# kb2040.net
KiCad netlist of a schematic drawn in EAGLE
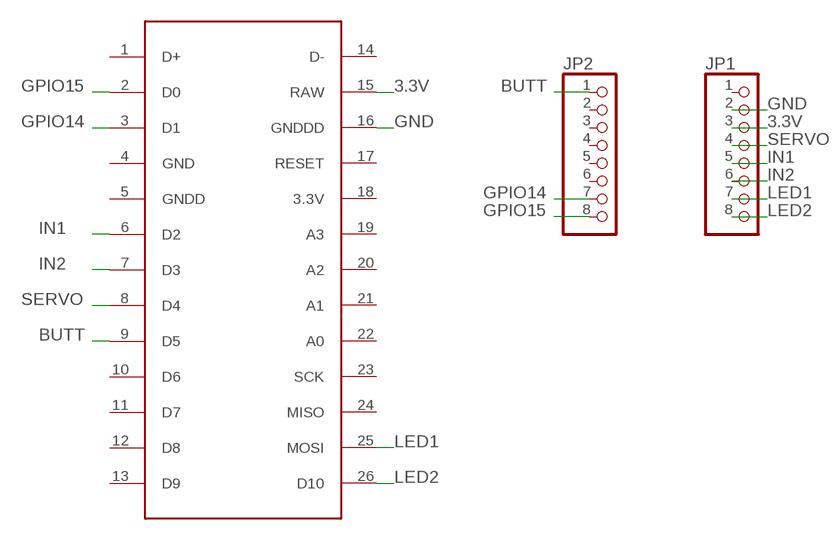
[diagram p0: schematic, sheet 1]

(export (version "E")
  (design (tool "Eeschema 10.0.6"))
  (components
    (comp (ref "JP1")
      (value "PINHD-1X8")
      (footprint "eagle-import:1X08")
      (libsource (lib "eagle-import") (part "PINHD-1X8"))
    )
    (comp (ref "JP2")
      (value "PINHD-1X8")
      (footprint "eagle-import:1X08")
      (libsource (lib "eagle-import") (part "PINHD-1X8"))
    )
    (comp (ref "U$1")
      (value "KB2040")
      (footprint "eagle-import:KB2040")
      (libsource (lib "eagle-import") (part "KB2040"))
    )
  )
  (nets
    (net (code "1") (name "/3.3V") (class "Default")
      (node (ref "JP1") (pin "3") (pinfunction "3_3") (pintype "passive"))
      (node (ref "U$1") (pin "15") (pinfunction "RAW_15") (pintype "bidirectional"))
    )
    (net (code "2") (name "/BUTT") (class "Default")
      (node (ref "JP2") (pin "1") (pinfunction "1_1") (pintype "passive"))
      (node (ref "U$1") (pin "9") (pinfunction "D5_9") (pintype "bidirectional"))
    )
    (net (code "3") (name "/GND") (class "Default")
      (node (ref "JP1") (pin "2") (pinfunction "2_2") (pintype "passive"))
      (node (ref "U$1") (pin "16") (pinfunction "GNDDD_16") (pintype "bidirectional"))
    )
    (net (code "4") (name "/GPIO14") (class "Default")
      (node (ref "JP2") (pin "7") (pinfunction "7_7") (pintype "passive"))
      (node (ref "U$1") (pin "3") (pinfunction "D1_3") (pintype "bidirectional"))
    )
    (net (code "5") (name "/GPIO15") (class "Default")
      (node (ref "JP2") (pin "8") (pinfunction "8_8") (pintype "passive"))
      (node (ref "U$1") (pin "2") (pinfunction "D0_2") (pintype "bidirectional"))
    )
    (net (code "6") (name "/IN1") (class "Default")
      (node (ref "JP1") (pin "5") (pinfunction "5_5") (pintype "passive"))
      (node (ref "U$1") (pin "6") (pinfunction "D2_6") (pintype "bidirectional"))
    )
    (net (code "7") (name "/IN2") (class "Default")
      (node (ref "JP1") (pin "6") (pinfunction "6_6") (pintype "passive"))
      (node (ref "U$1") (pin "7") (pinfunction "D3_7") (pintype "bidirectional"))
    )
    (net (code "8") (name "/LED1") (class "Default")
      (node (ref "JP1") (pin "7") (pinfunction "7_7") (pintype "passive"))
      (node (ref "U$1") (pin "25") (pinfunction "MOSI_25") (pintype "bidirectional"))
    )
    (net (code "9") (name "/LED2") (class "Default")
      (node (ref "JP1") (pin "8") (pinfunction "8_8") (pintype "passive"))
      (node (ref "U$1") (pin "26") (pinfunction "D10_26") (pintype "bidirectional"))
    )
    (net (code "10") (name "/SERVO") (class "Default")
      (node (ref "JP1") (pin "4") (pinfunction "4_4") (pintype "passive"))
      (node (ref "U$1") (pin "8") (pinfunction "D4_8") (pintype "bidirectional"))
    )
    (net (code "11") (name "unconnected-(JP1-Pad1)") (class "Default")
      (node (ref "JP1") (pin "1") (pinfunction "1_1") (pintype "passive"))
    )
    (net (code "12") (name "unconnected-(JP2-Pad2)") (class "Default")
      (node (ref "JP2") (pin "2") (pinfunction "2_2") (pintype "passive"))
    )
    (net (code "13") (name "unconnected-(JP2-Pad3)") (class "Default")
      (node (ref "JP2") (pin "3") (pinfunction "3_3") (pintype "passive"))
    )
    (net (code "14") (name "unconnected-(JP2-Pad4)") (class "Default")
      (node (ref "JP2") (pin "4") (pinfunction "4_4") (pintype "passive"))
    )
    (net (code "15") (name "unconnected-(JP2-Pad5)") (class "Default")
      (node (ref "JP2") (pin "5") (pinfunction "5_5") (pintype "passive"))
    )
    (net (code "16") (name "unconnected-(JP2-Pad6)") (class "Default")
      (node (ref "JP2") (pin "6") (pinfunction "6_6") (pintype "passive"))
    )
    (net (code "17") (name "unconnected-(U$1-3.3V-Pad18)") (class "Default")
      (node (ref "U$1") (pin "18") (pinfunction "3.3V_18") (pintype "bidirectional"))
    )
    (net (code "18") (name "unconnected-(U$1-A0-Pad22)") (class "Default")
      (node (ref "U$1") (pin "22") (pinfunction "A0_22") (pintype "bidirectional"))
    )
    (net (code "19") (name "unconnected-(U$1-A1-Pad21)") (class "Default")
      (node (ref "U$1") (pin "21") (pinfunction "A1_21") (pintype "bidirectional"))
    )
    (net (code "20") (name "unconnected-(U$1-A2-Pad20)") (class "Default")
      (node (ref "U$1") (pin "20") (pinfunction "A2_20") (pintype "bidirectional"))
    )
    (net (code "21") (name "unconnected-(U$1-A3-Pad19)") (class "Default")
      (node (ref "U$1") (pin "19") (pinfunction "A3_19") (pintype "bidirectional"))
    )
    (net (code "22") (name "unconnected-(U$1-D+-Pad1)") (class "Default")
      (node (ref "U$1") (pin "1") (pinfunction "D+_1") (pintype "bidirectional"))
    )
    (net (code "23") (name "unconnected-(U$1-D--Pad14)") (class "Default")
      (node (ref "U$1") (pin "14") (pinfunction "D-_14") (pintype "bidirectional"))
    )
    (net (code "24") (name "unconnected-(U$1-D6-Pad10)") (class "Default")
      (node (ref "U$1") (pin "10") (pinfunction "D6_10") (pintype "bidirectional"))
    )
    (net (code "25") (name "unconnected-(U$1-D7-Pad11)") (class "Default")
      (node (ref "U$1") (pin "11") (pinfunction "D7_11") (pintype "bidirectional"))
    )
    (net (code "26") (name "unconnected-(U$1-D8-Pad12)") (class "Default")
      (node (ref "U$1") (pin "12") (pinfunction "D8_12") (pintype "bidirectional"))
    )
    (net (code "27") (name "unconnected-(U$1-D9-Pad13)") (class "Default")
      (node (ref "U$1") (pin "13") (pinfunction "D9_13") (pintype "bidirectional"))
    )
    (net (code "28") (name "unconnected-(U$1-GND-Pad4)") (class "Default")
      (node (ref "U$1") (pin "4") (pinfunction "GND_4") (pintype "bidirectional"))
    )
    (net (code "29") (name "unconnected-(U$1-GNDD-Pad5)") (class "Default")
      (node (ref "U$1") (pin "5") (pinfunction "GNDD_5") (pintype "bidirectional"))
    )
    (net (code "30") (name "unconnected-(U$1-MISO-Pad24)") (class "Default")
      (node (ref "U$1") (pin "24") (pinfunction "MISO_24") (pintype "bidirectional"))
    )
    (net (code "31") (name "unconnected-(U$1-RESET-Pad17)") (class "Default")
      (node (ref "U$1") (pin "17") (pinfunction "RESET_17") (pintype "bidirectional"))
    )
    (net (code "32") (name "unconnected-(U$1-SCK-Pad23)") (class "Default")
      (node (ref "U$1") (pin "23") (pinfunction "SCK_23") (pintype "bidirectional"))
    )
  )
)
